# ESP01-1wire.net
KiCad netlist of a schematic drawn in EAGLE
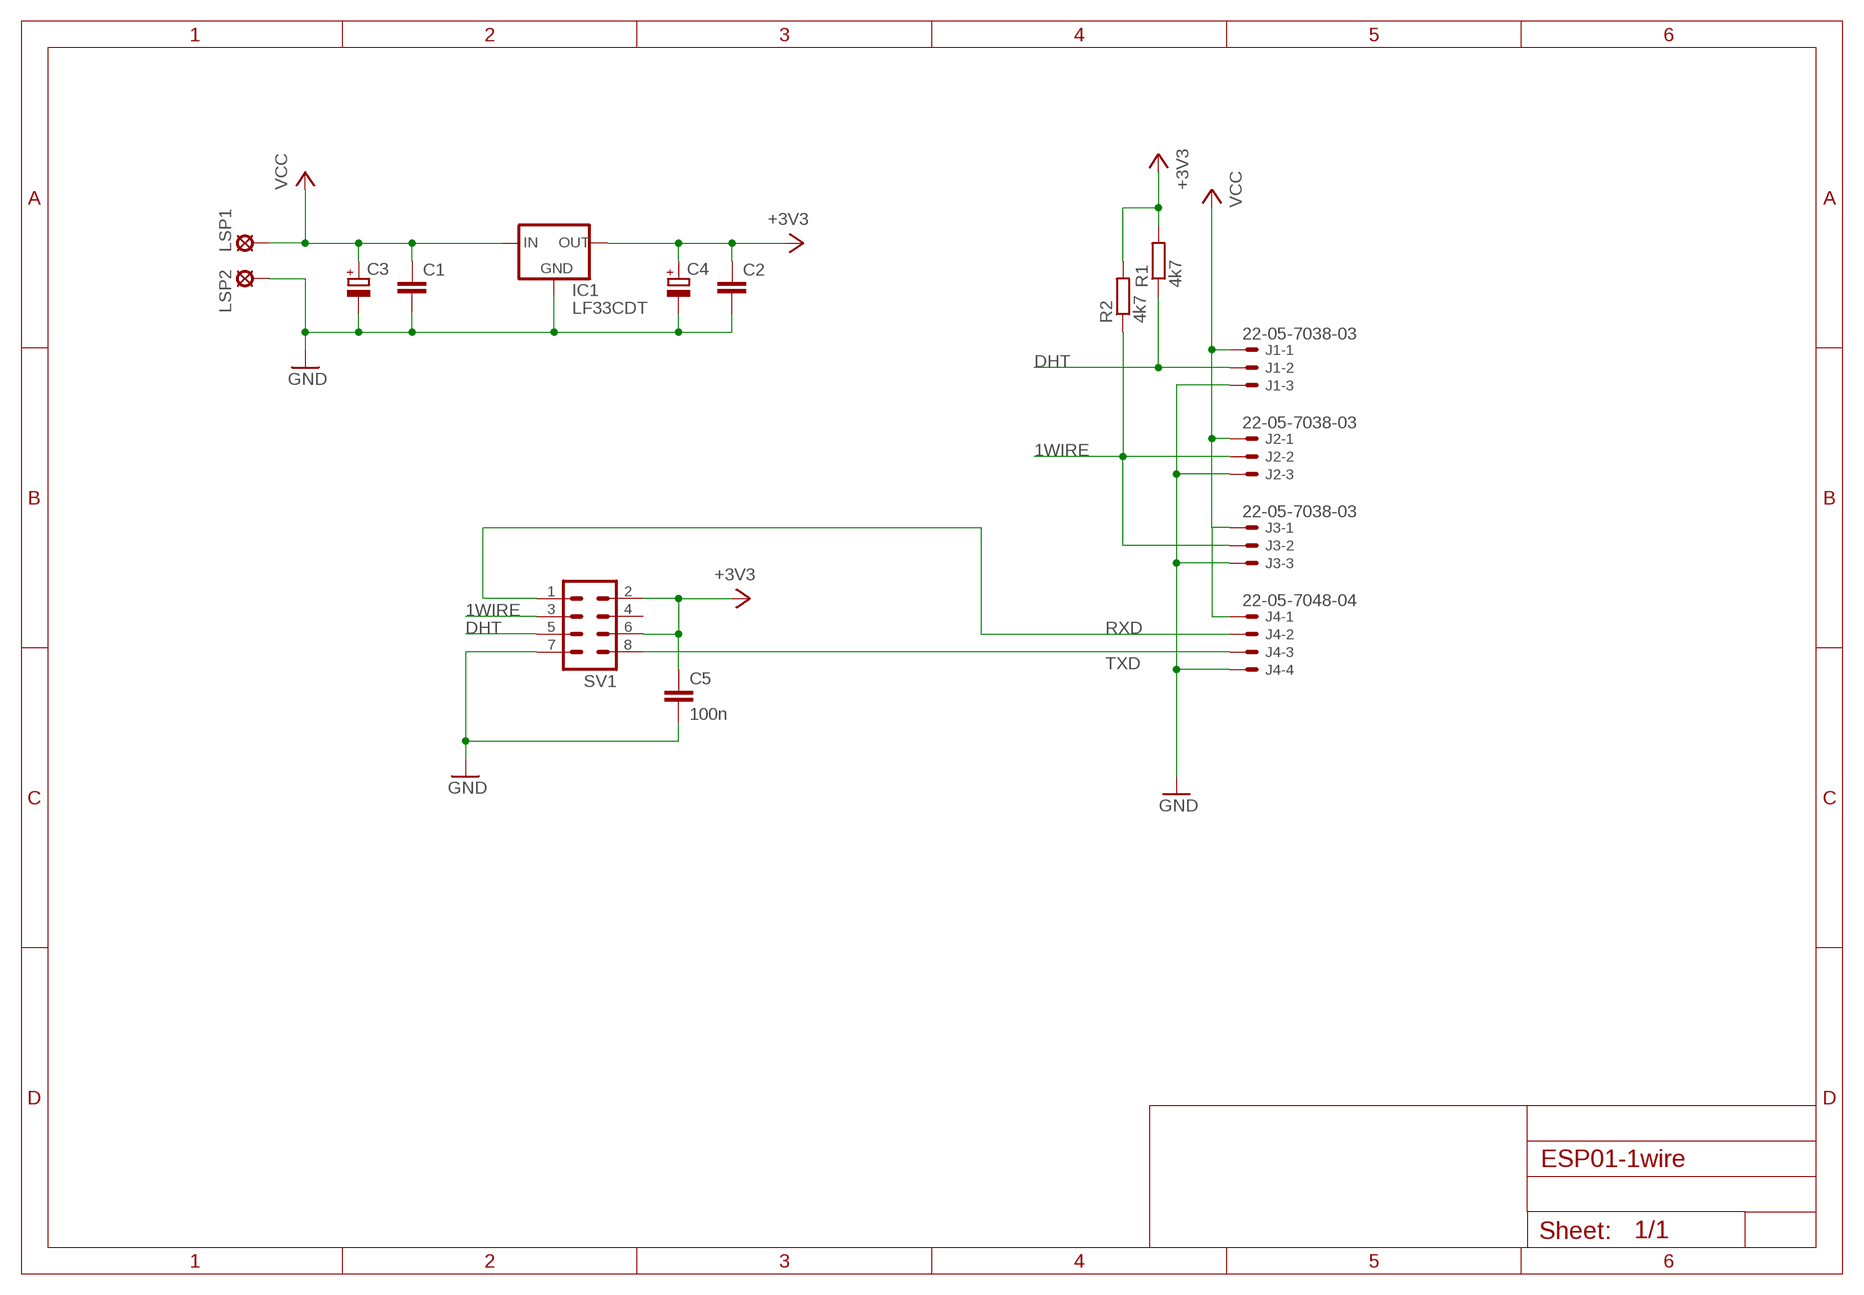
[diagram p0: schematic, sheet 1]

(export (version "E")
  (design (tool "Eeschema 10.0.6"))
  (components
    (comp (ref "C1")
      (value "C-EUC0805")
      (footprint "eagle-import:C0805")
      (libsource (lib "eagle-import") (part "C-EUC0805"))
    )
    (comp (ref "C2")
      (value "C-EUC0805")
      (footprint "eagle-import:C0805")
      (libsource (lib "eagle-import") (part "C-EUC0805"))
    )
    (comp (ref "C3")
      (value "CPOL-EUSMCA")
      (footprint "eagle-import:SMC_A")
      (libsource (lib "eagle-import") (part "CPOL-EUSMCA"))
    )
    (comp (ref "C4")
      (value "CPOL-EUSMCA")
      (footprint "eagle-import:SMC_A")
      (libsource (lib "eagle-import") (part "CPOL-EUSMCA"))
    )
    (comp (ref "C5")
      (value "100n")
      (footprint "eagle-import:C0805")
      (libsource (lib "eagle-import") (part "C-EUC0805"))
    )
    (comp (ref "IC1")
      (value "LF33CDT")
      (footprint "eagle-import:DPACK")
      (libsource (lib "eagle-import") (part "LP2950?CDT-3.3"))
    )
    (comp (ref "J1")
      (value "22-05-7038-03")
      (footprint "eagle-import:7395-03")
      (libsource (lib "eagle-import") (part "22-?-0305-7038"))
    )
    (comp (ref "J2")
      (value "22-05-7038-03")
      (footprint "eagle-import:7395-03")
      (libsource (lib "eagle-import") (part "22-?-0305-7038"))
    )
    (comp (ref "J3")
      (value "22-05-7038-03")
      (footprint "eagle-import:7395-03")
      (libsource (lib "eagle-import") (part "22-?-0305-7038"))
    )
    (comp (ref "J4")
      (value "22-05-7048-04")
      (footprint "eagle-import:7395-04")
      (libsource (lib "eagle-import") (part "22-?-0405-7048"))
    )
    (comp (ref "LSP1")
      (value "LSP10")
      (footprint "eagle-import:LSP10")
      (libsource (lib "eagle-import") (part "LSP10"))
    )
    (comp (ref "LSP2")
      (value "LSP10")
      (footprint "eagle-import:LSP10")
      (libsource (lib "eagle-import") (part "LSP10"))
    )
    (comp (ref "R1")
      (value "4k7")
      (footprint "eagle-import:R0805")
      (libsource (lib "eagle-import") (part "R-EU_R0805"))
    )
    (comp (ref "R2")
      (value "4k7")
      (footprint "eagle-import:R0805")
      (libsource (lib "eagle-import") (part "R-EU_R0805"))
    )
    (comp (ref "SV1")
      (value "MA04-2")
      (footprint "eagle-import:MA04-2")
      (libsource (lib "eagle-import") (part "MA04-2"))
    )
  )
  (nets
    (net (code "1") (name "+3V3") (class "Default")
      (node (ref "C2") (pin "1") (pinfunction "1_1") (pintype "passive"))
      (node (ref "C4") (pin "+") (pinfunction "+_+") (pintype "passive"))
      (node (ref "C5") (pin "1") (pinfunction "1_1") (pintype "passive"))
      (node (ref "IC1") (pin "3") (pinfunction "OUT_3") (pintype "passive"))
      (node (ref "R1") (pin "2") (pinfunction "2_2") (pintype "passive"))
      (node (ref "R2") (pin "2") (pinfunction "2_2") (pintype "passive"))
      (node (ref "SV1") (pin "2") (pinfunction "2_2") (pintype "passive"))
      (node (ref "SV1") (pin "6") (pinfunction "6_6") (pintype "passive"))
    )
    (net (code "2") (name "/1WIRE") (class "Default")
      (node (ref "J2") (pin "2") (pinfunction "S_2") (pintype "passive"))
      (node (ref "J3") (pin "2") (pinfunction "S_2") (pintype "passive"))
      (node (ref "R2") (pin "1") (pinfunction "1_1") (pintype "passive"))
      (node (ref "SV1") (pin "3") (pinfunction "3_3") (pintype "passive"))
    )
    (net (code "3") (name "/DHT") (class "Default")
      (node (ref "J1") (pin "2") (pinfunction "S_2") (pintype "passive"))
      (node (ref "R1") (pin "1") (pinfunction "1_1") (pintype "passive"))
      (node (ref "SV1") (pin "5") (pinfunction "5_5") (pintype "passive"))
    )
    (net (code "4") (name "/RXD") (class "Default")
      (node (ref "J4") (pin "2") (pinfunction "S_2") (pintype "passive"))
      (node (ref "SV1") (pin "1") (pinfunction "1_1") (pintype "passive"))
    )
    (net (code "5") (name "/TXD") (class "Default")
      (node (ref "J4") (pin "3") (pinfunction "S_3") (pintype "passive"))
      (node (ref "SV1") (pin "8") (pinfunction "8_8") (pintype "passive"))
    )
    (net (code "6") (name "GND") (class "Default")
      (node (ref "C1") (pin "2") (pinfunction "2_2") (pintype "passive"))
      (node (ref "C2") (pin "2") (pinfunction "2_2") (pintype "passive"))
      (node (ref "C3") (pin "-") (pinfunction "-_-") (pintype "passive"))
      (node (ref "C4") (pin "-") (pinfunction "-_-") (pintype "passive"))
      (node (ref "C5") (pin "2") (pinfunction "2_2") (pintype "passive"))
      (node (ref "IC1") (pin "4") (pinfunction "GND_4") (pintype "input"))
      (node (ref "J1") (pin "3") (pinfunction "S_3") (pintype "passive"))
      (node (ref "J2") (pin "3") (pinfunction "S_3") (pintype "passive"))
      (node (ref "J3") (pin "3") (pinfunction "S_3") (pintype "passive"))
      (node (ref "J4") (pin "4") (pinfunction "S_4") (pintype "passive"))
      (node (ref "LSP2") (pin "MP") (pinfunction "MP_MP") (pintype "passive"))
      (node (ref "SV1") (pin "7") (pinfunction "7_7") (pintype "passive"))
    )
    (net (code "7") (name "VCC") (class "Default")
      (node (ref "C1") (pin "1") (pinfunction "1_1") (pintype "passive"))
      (node (ref "C3") (pin "+") (pinfunction "+_+") (pintype "passive"))
      (node (ref "IC1") (pin "1") (pinfunction "IN_1") (pintype "input"))
      (node (ref "J1") (pin "1") (pinfunction "S_1") (pintype "passive"))
      (node (ref "J2") (pin "1") (pinfunction "S_1") (pintype "passive"))
      (node (ref "J3") (pin "1") (pinfunction "S_1") (pintype "passive"))
      (node (ref "J4") (pin "1") (pinfunction "S_1") (pintype "passive"))
      (node (ref "LSP1") (pin "MP") (pinfunction "MP_MP") (pintype "passive"))
    )
    (net (code "8") (name "unconnected-(SV1-Pad4)") (class "Default")
      (node (ref "SV1") (pin "4") (pinfunction "4_4") (pintype "passive"))
    )
  )
)
